# DRV8323RSRGZR.net
KiCad netlist of a schematic drawn in Altium Designer
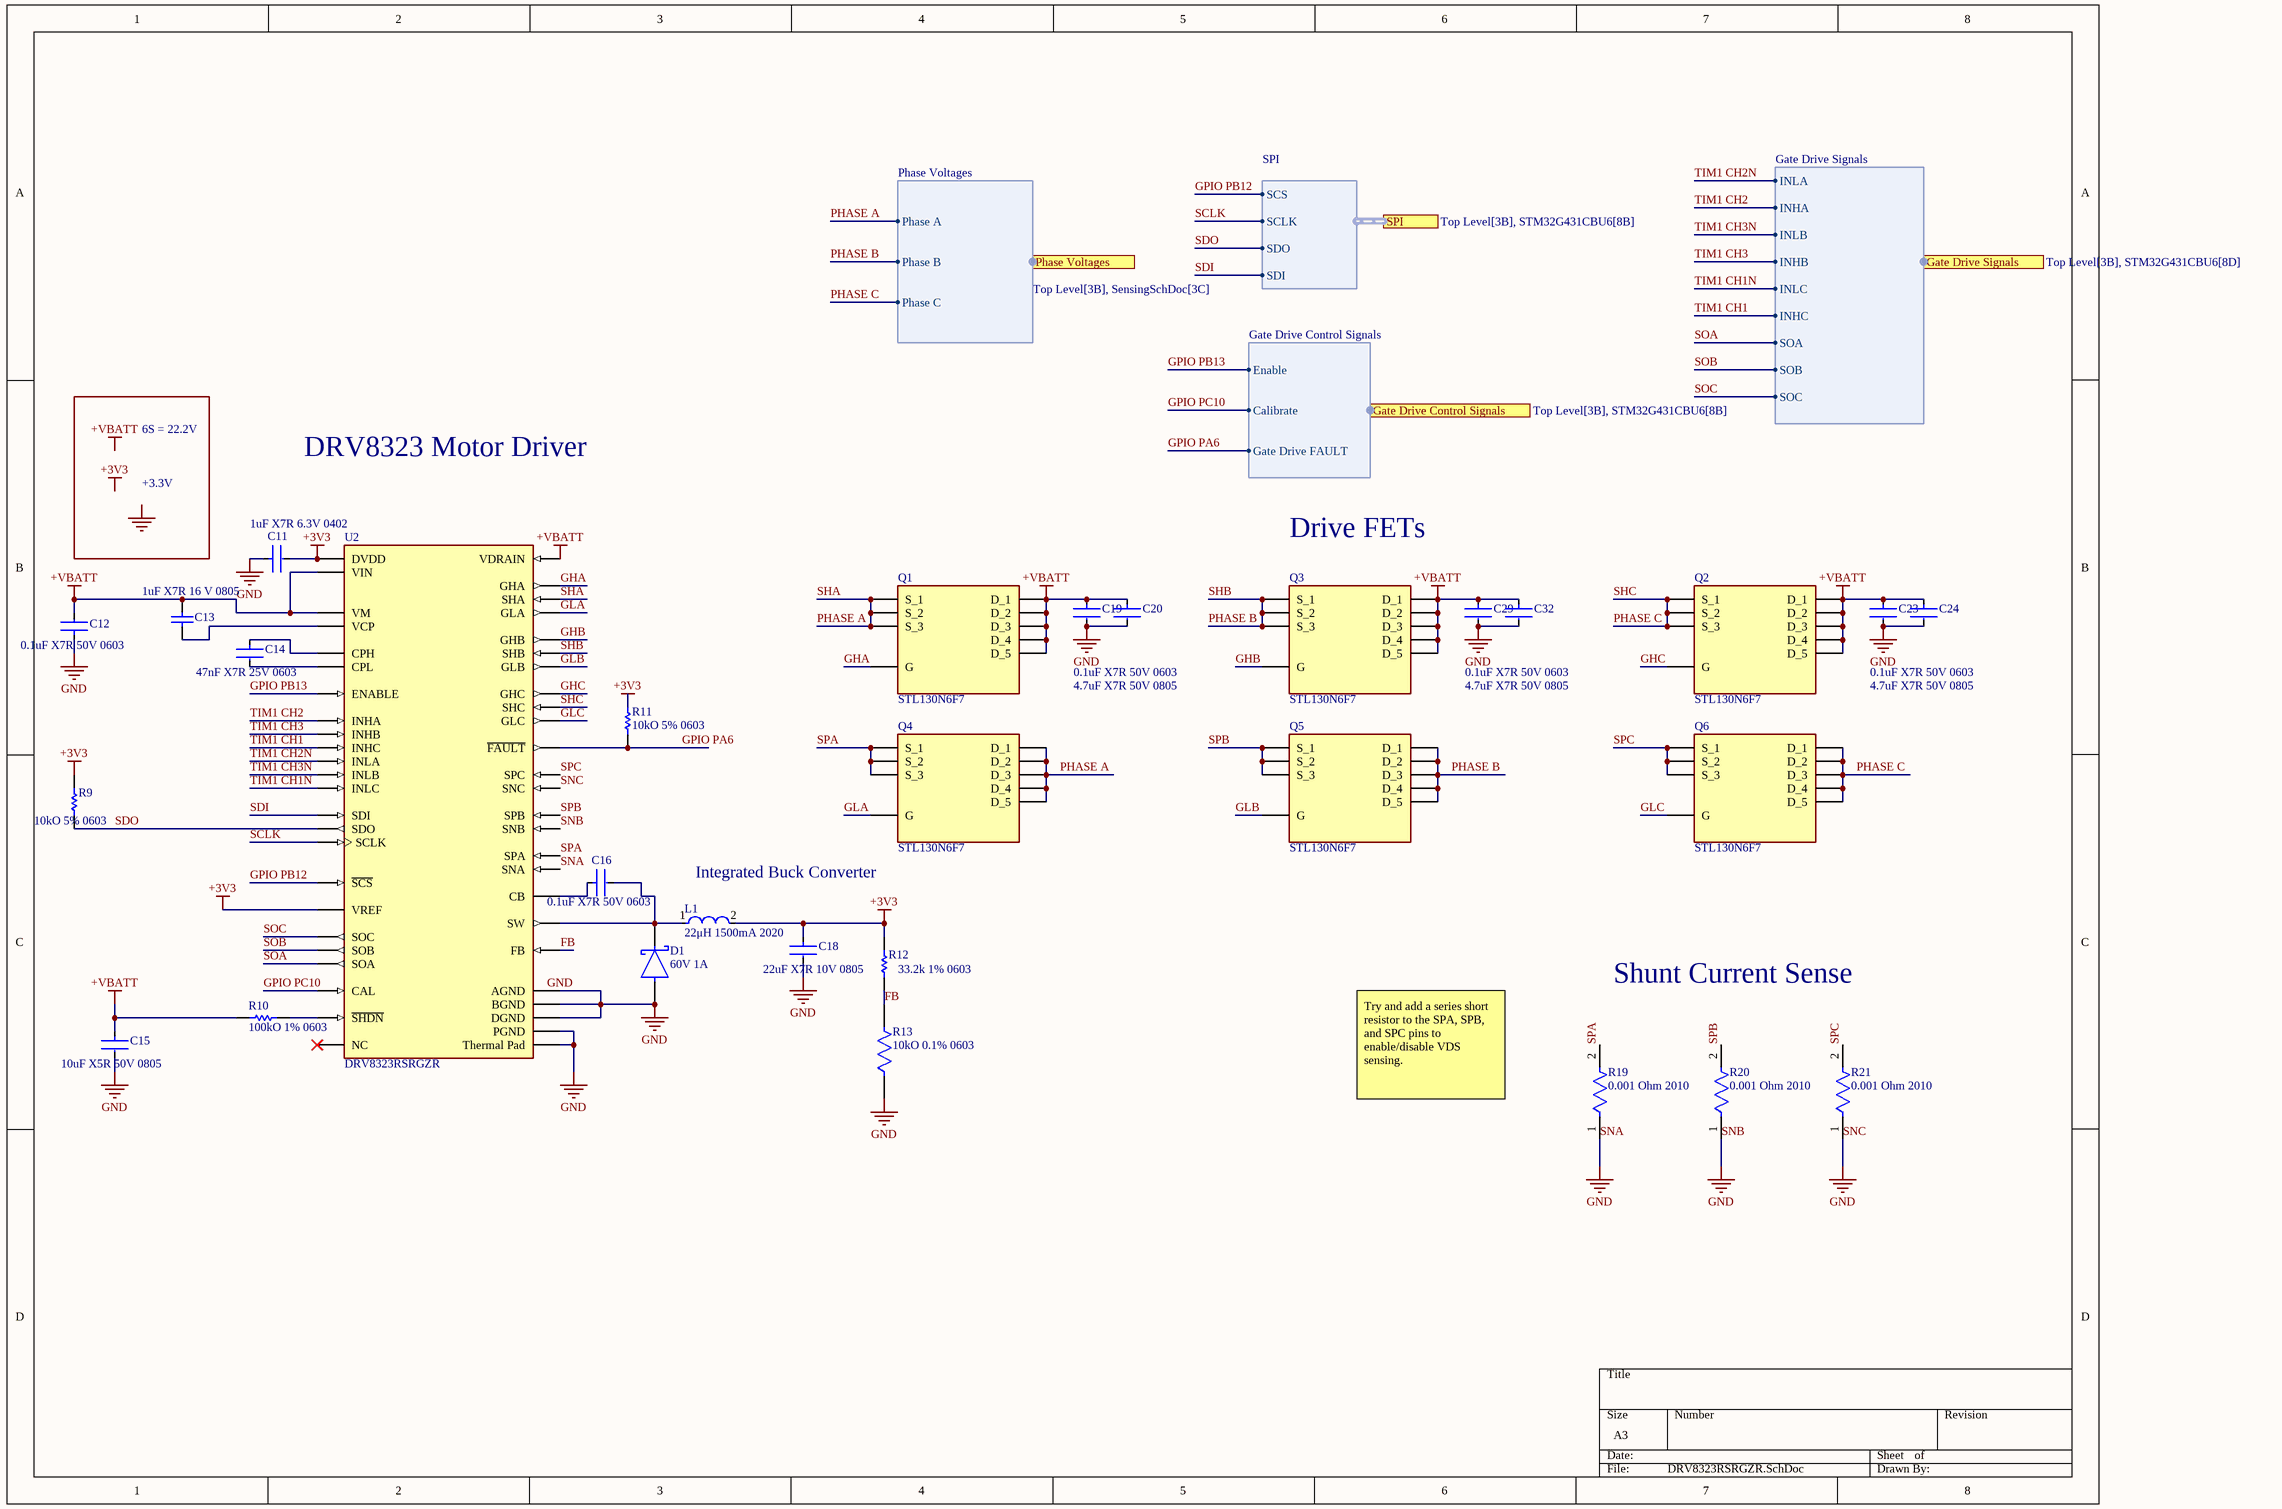
[diagram p0: DRV8323RSRGZR.SchDoc]

(export (version "E")
  (design (tool "Eeschema 10.0.6"))
  (components
    (comp (ref "C11")
      (value "1uF X7R 6.3V 0402")
      (footprint "FP-GRT155-0_05-IPC_C")
      (description "Multi-Layer Ceramic Capacitor 1uF 6.3V X7R ±10% 0402 Paper T/R")
      (libsource (lib "Altium Content Vault") (part "02cd4be3c70576c341d710602a673aa"))
    )
    (comp (ref "C12")
      (value "0.1uF X7R 50V 0603")
      (footprint "FP-0603B104K500CT-IPC_C")
      (description "CAP CER 0.1UF 50V X7R 0603")
      (fields (field (name "TOLERANCE") "10%"))
      (libsource (lib "Altium Content Vault") (part "02cd4be3c70576c341d710602a673aa"))
    )
    (comp (ref "C13")
      (value "1uF X7R 16 V 0805")
      (footprint "CAPC2013X140X50NL20T25")
      (fields (field (name "PART NUMBER") "C0805C105J4RACTU") (field (name "MANUFACTURER") "Kemet"))
      (libsource (lib "Altium Content Vault") (part "CAP"))
    )
    (comp (ref "C14")
      (value "47nF X7R 25V 0603")
      (footprint "FP-C0603C-CF-MFG")
      (description "CAP CER 0.047UF 25V 10% X7R 0603")
      (fields
        (field (name "MANUFACTURER") "KEMET")
        (field (name "OCTOPART") "https://octopart.com/c0603c473k3ractu-kemet-3834514")
      )
      (libsource (lib "Altium Content Vault") (part "b4654b650e69147ec39a6b967a45e02"))
    )
    (comp (ref "C15")
      (value "10uF X5R 50V 0805")
      (footprint "FP-GRM21B-0_2-e0_2_0_7-IPC_A")
      (description "Chip Multilayer Ceramic Capacitors for General Purpose, 0805, 10uF, X5R, 15%, 10%, 50V")
      (fields (field (name "TOLERANCE") "10%"))
      (libsource (lib "Altium Content Vault") (part "b4654b650e69147ec39a6b967a45e02"))
    )
    (comp (ref "C16")
      (value "0.1uF X7R 50V 0603")
      (footprint "FP-0603B104K500CT-IPC_C")
      (description "CAP CER 0.1UF 50V X7R 0603")
      (fields (field (name "TOLERANCE") "10%"))
      (libsource (lib "Altium Content Vault") (part "02cd4be3c70576c341d710602a673aa"))
    )
    (comp (ref "C18")
      (value "22uF X7R 10V 0805")
      (footprint "FP-GRM21B-0_2-e0_2_0_7-MFG")
      (description "Chip Multilayer Ceramic Capacitors for General Purpose, 0805, 22uF, X7R, 15%, 20%, 10V")
      (libsource (lib "Altium Content Vault") (part "b4654b650e69147ec39a6b967a45e02"))
    )
    (comp (ref "C19")
      (value "0.1uF X7R 50V 0603")
      (footprint "FP-0603B104K500CT-IPC_C")
      (description "CAP CER 0.1UF 50V X7R 0603")
      (fields (field (name "TOLERANCE") "10%"))
      (libsource (lib "Altium Content Vault") (part "02cd4be3c70576c341d710602a673aa"))
    )
    (comp (ref "C20")
      (value "4.7uF X7R 50V 0805")
      (footprint "FP-GRM21B-0_2-e0_2_0_7-MFG")
      (description "Chip Multilayer Ceramic Capacitors for General Purpose, 0805, 4.7uF, X7R, 15%, 20%, 50V")
      (libsource (lib "Altium Content Vault") (part "b4654b650e69147ec39a6b967a45e02"))
    )
    (comp (ref "C23")
      (value "0.1uF X7R 50V 0603")
      (footprint "FP-0603B104K500CT-IPC_C")
      (description "CAP CER 0.1UF 50V X7R 0603")
      (fields (field (name "TOLERANCE") "10%"))
      (libsource (lib "Altium Content Vault") (part "02cd4be3c70576c341d710602a673aa"))
    )
    (comp (ref "C24")
      (value "4.7uF X7R 50V 0805")
      (footprint "FP-GRM21B-0_2-e0_2_0_7-MFG")
      (description "Chip Multilayer Ceramic Capacitors for General Purpose, 0805, 4.7uF, X7R, 15%, 20%, 50V")
      (libsource (lib "Altium Content Vault") (part "b4654b650e69147ec39a6b967a45e02"))
    )
    (comp (ref "C29")
      (value "0.1uF X7R 50V 0603")
      (footprint "FP-0603B104K500CT-IPC_C")
      (description "CAP CER 0.1UF 50V X7R 0603")
      (fields (field (name "TOLERANCE") "10%"))
      (libsource (lib "Altium Content Vault") (part "02cd4be3c70576c341d710602a673aa"))
    )
    (comp (ref "C32")
      (value "4.7uF X7R 50V 0805")
      (footprint "FP-GRM21B-0_2-e0_2_0_7-MFG")
      (description "Chip Multilayer Ceramic Capacitors for General Purpose, 0805, 4.7uF, X7R, 15%, 20%, 50V")
      (libsource (lib "Altium Content Vault") (part "b4654b650e69147ec39a6b967a45e02"))
    )
    (comp (ref "D1")
      (value "60V 1A")
      (footprint "FP-SMA-MFG")
      (description "DIODE SCHOTTKY 60V 1A SMA")
      (libsource (lib "Altium Content Vault") (part "1d6ec82d83fb6aee721767c19dac4b9"))
    )
    (comp (ref "L1")
      (value "22μH 1500mA 2020")
      (footprint "FP-LQH5BPN_38-MFG")
      (description "Wire Wound Ferrite Inductor for Power Lines 22μH ±20% 0.132Ω 1500mA 2020\r\nLQH5BPN220M38L")
      (libsource (lib "Altium Content Vault") (part "725321dda6339637d4d059423bc1c3c"))
    )
    (comp (ref "Q1")
      (value "STL130N6F7")
      (footprint "FERD20U50DJFTR")
      (description "MOSFET (N-Channel)")
      (fields (field (name "MOUSER PART NUMBER") "511-STL130N6F7"))
      (libsource (lib "Schlib1") (part "STL130N6F7"))
    )
    (comp (ref "Q2")
      (value "STL130N6F7")
      (footprint "FERD20U50DJFTR")
      (description "MOSFET (N-Channel)")
      (fields (field (name "MOUSER PART NUMBER") "511-STL130N6F7"))
      (libsource (lib "Schlib1") (part "STL130N6F7"))
    )
    (comp (ref "Q3")
      (value "STL130N6F7")
      (footprint "FERD20U50DJFTR")
      (description "MOSFET (N-Channel)")
      (fields (field (name "MOUSER PART NUMBER") "511-STL130N6F7"))
      (libsource (lib "Schlib1") (part "STL130N6F7"))
    )
    (comp (ref "Q4")
      (value "STL130N6F7")
      (footprint "FERD20U50DJFTR")
      (description "MOSFET (N-Channel)")
      (fields (field (name "MOUSER PART NUMBER") "511-STL130N6F7"))
      (libsource (lib "Schlib1") (part "STL130N6F7"))
    )
    (comp (ref "Q5")
      (value "STL130N6F7")
      (footprint "FERD20U50DJFTR")
      (description "MOSFET (N-Channel)")
      (fields (field (name "MOUSER PART NUMBER") "511-STL130N6F7"))
      (libsource (lib "Schlib1") (part "STL130N6F7"))
    )
    (comp (ref "Q6")
      (value "STL130N6F7")
      (footprint "FERD20U50DJFTR")
      (description "MOSFET (N-Channel)")
      (fields (field (name "MOUSER PART NUMBER") "511-STL130N6F7"))
      (libsource (lib "Schlib1") (part "STL130N6F7"))
    )
    (comp (ref "R9")
      (value "10kO 5% 0603")
      (footprint "RESC1608X55X25LL10T15")
      (fields (field (name "MANUFACTURER") "Yageo") (field (name "PART NUMBER") "RC0603JR-1010KL"))
      (libsource (lib "Altium Content Vault") (part "RES"))
    )
    (comp (ref "R10")
      (value "100kO 1% 0603")
      (footprint "RESC1608X55X25ML10T15")
      (fields (field (name "MANUFACTURER") "Yageo") (field (name "PART NUMBER") "RC0603FR-13100KL"))
      (libsource (lib "Altium Content Vault") (part "RES"))
    )
    (comp (ref "R11")
      (value "10kO 5% 0603")
      (footprint "RESC1608X55X25LL10T15")
      (fields (field (name "MANUFACTURER") "Yageo") (field (name "PART NUMBER") "RC0603JR-1010KL"))
      (libsource (lib "Altium Content Vault") (part "RES"))
    )
    (comp (ref "R12")
      (value "33.2k 1% 0603")
      (footprint "RESC1608X55X25NL10T15")
      (description "Chip Resistor, 33.2 KOhm, +/- 1%, 100 mW, -55 to 155 degC, 0603 (1608 Metric), RoHS, Tape and Reel")
      (fields (field (name "TOLERANCE") "20ppm"))
      (libsource (lib "Altium Content Vault") (part "RES-2"))
    )
    (comp (ref "R13")
      (value "10kO 0.1% 0603")
      (footprint "FP-RT0603-MFG")
      (description "RES SMD 10K OHM 0.1% 1/10W 0603")
      (fields (field (name "MANUFACTURER") "Yageo") (field (name "TOLERANCE") "0.001"))
      (libsource (lib "") (part "1029c3af85768c4190bb7ad29bc67b5_1"))
    )
    (comp (ref "R19")
      (value "0.001 Ohm 2010")
      (footprint "FP-WSL2010-1_47-MFG")
      (fields (field (name "TOLERANCE") "1%"))
      (libsource (lib "Altium Content Vault") (part "1029c3af85768c4190bb7ad29bc67b5"))
    )
    (comp (ref "R20")
      (value "0.001 Ohm 2010")
      (footprint "FP-WSL2010-1_47-MFG")
      (fields (field (name "TOLERANCE") "1%"))
      (libsource (lib "Altium Content Vault") (part "1029c3af85768c4190bb7ad29bc67b5"))
    )
    (comp (ref "R21")
      (value "0.001 Ohm 2010")
      (footprint "FP-WSL2010-1_47-MFG")
      (fields (field (name "TOLERANCE") "1%"))
      (libsource (lib "Altium Content Vault") (part "1029c3af85768c4190bb7ad29bc67b5"))
    )
    (comp (ref "U2")
      (value "DRV8323RSRGZR")
      (footprint "FP-RGZ0048A-MFG")
      (description "IC MTR DRV MULTIPHAS 6-60V 48QFN")
      (fields
        (field (name "MANUFACTURER") "Texas Instruments")
        (field (name "OCTOPART") "https://octopart.com/drv8323rsrgzr-texas+instruments-80665177")
      )
      (libsource (lib "Altium Content Vault") (part "9f6f2f4cce60835f155f5fba280b04a"))
    )
  )
  (nets
    (net (code "8") (name "+3V3") (class "Default")
      (node (ref "C11") (pin "2") (pinfunction "2_2") (pintype "passive"))
      (node (ref "C18") (pin "1") (pinfunction "1_1") (pintype "passive"))
      (node (ref "L1") (pin "2") (pinfunction "2_2") (pintype "passive"))
      (node (ref "R11") (pin "2") (pinfunction "2_2") (pintype "passive"))
      (node (ref "R12") (pin "2") (pinfunction "2_2") (pintype "passive"))
      (node (ref "R9") (pin "2") (pinfunction "2_2") (pintype "passive"))
      (node (ref "U2") (pin "26") (pinfunction "VREF_26") (pintype "power_in"))
      (node (ref "U2") (pin "36") (pinfunction "DVDD_36") (pintype "power_in"))
    )
    (net (code "9") (name "+VBATT") (class "Default")
      (node (ref "C12") (pin "2") (pinfunction "2_2") (pintype "passive"))
      (node (ref "C13") (pin "1") (pinfunction "1_1") (pintype "passive"))
      (node (ref "C15") (pin "1") (pinfunction "1_1") (pintype "passive"))
      (node (ref "C19") (pin "1") (pinfunction "1_1") (pintype "passive"))
      (node (ref "C20") (pin "1") (pinfunction "1_1") (pintype "passive"))
      (node (ref "C23") (pin "1") (pinfunction "1_1") (pintype "passive"))
      (node (ref "C24") (pin "1") (pinfunction "1_1") (pintype "passive"))
      (node (ref "C29") (pin "1") (pinfunction "1_1") (pintype "passive"))
      (node (ref "C32") (pin "1") (pinfunction "1_1") (pintype "passive"))
      (node (ref "Q1") (pin "5") (pinfunction "D_1_5") (pintype "passive"))
      (node (ref "Q1") (pin "6") (pinfunction "D_2_6") (pintype "passive"))
      (node (ref "Q1") (pin "7") (pinfunction "D_3_7") (pintype "passive"))
      (node (ref "Q1") (pin "8") (pinfunction "D_4_8") (pintype "passive"))
      (node (ref "Q1") (pin "9") (pinfunction "D_5_9") (pintype "passive"))
      (node (ref "Q2") (pin "5") (pinfunction "D_1_5") (pintype "passive"))
      (node (ref "Q2") (pin "6") (pinfunction "D_2_6") (pintype "passive"))
      (node (ref "Q2") (pin "7") (pinfunction "D_3_7") (pintype "passive"))
      (node (ref "Q2") (pin "8") (pinfunction "D_4_8") (pintype "passive"))
      (node (ref "Q2") (pin "9") (pinfunction "D_5_9") (pintype "passive"))
      (node (ref "Q3") (pin "5") (pinfunction "D_1_5") (pintype "passive"))
      (node (ref "Q3") (pin "6") (pinfunction "D_2_6") (pintype "passive"))
      (node (ref "Q3") (pin "7") (pinfunction "D_3_7") (pintype "passive"))
      (node (ref "Q3") (pin "8") (pinfunction "D_4_8") (pintype "passive"))
      (node (ref "Q3") (pin "9") (pinfunction "D_5_9") (pintype "passive"))
      (node (ref "R10") (pin "2") (pinfunction "2_2") (pintype "passive"))
      (node (ref "U2") (pin "47") (pinfunction "VIN_47") (pintype "power_in"))
      (node (ref "U2") (pin "6") (pinfunction "VM_6") (pintype "power_in"))
      (node (ref "U2") (pin "7") (pinfunction "VDRAIN_7") (pintype "input"))
    )
    (net (code "10") (name "/FB") (class "Default")
      (node (ref "R12") (pin "1") (pinfunction "1_1") (pintype "passive"))
      (node (ref "R13") (pin "2") (pinfunction "2_2") (pintype "passive"))
      (node (ref "U2") (pin "1") (pinfunction "FB_1") (pintype "input"))
    )
    (net (code "11") (name "/GHA") (class "Default")
      (node (ref "Q1") (pin "4") (pinfunction "G_4") (pintype "passive"))
      (node (ref "U2") (pin "8") (pinfunction "GHA_8") (pintype "output"))
    )
    (net (code "12") (name "/GHB") (class "Default")
      (node (ref "Q3") (pin "4") (pinfunction "G_4") (pintype "passive"))
      (node (ref "U2") (pin "17") (pinfunction "GHB_17") (pintype "output"))
    )
    (net (code "13") (name "/GHC") (class "Default")
      (node (ref "Q2") (pin "4") (pinfunction "G_4") (pintype "passive"))
      (node (ref "U2") (pin "18") (pinfunction "GHC_18") (pintype "output"))
    )
    (net (code "14") (name "/GLA") (class "Default")
      (node (ref "Q4") (pin "4") (pinfunction "G_4") (pintype "passive"))
      (node (ref "U2") (pin "10") (pinfunction "GLA_10") (pintype "output"))
    )
    (net (code "15") (name "/GLB") (class "Default")
      (node (ref "Q5") (pin "4") (pinfunction "G_4") (pintype "passive"))
      (node (ref "U2") (pin "15") (pinfunction "GLB_15") (pintype "output"))
    )
    (net (code "16") (name "/GLC") (class "Default")
      (node (ref "Q6") (pin "4") (pinfunction "G_4") (pintype "passive"))
      (node (ref "U2") (pin "20") (pinfunction "GLC_20") (pintype "output"))
    )
    (net (code "17") (name "/GPIO PA6") (class "Default")
      (node (ref "R11") (pin "1") (pinfunction "1_1") (pintype "passive"))
      (node (ref "U2") (pin "28") (pinfunction "~{FAULT}_28") (pintype "output"))
    )
    (net (code "18") (name "/GPIO PB12") (class "Default")
      (node (ref "U2") (pin "32") (pinfunction "~{SCS}_32") (pintype "input"))
    )
    (net (code "19") (name "/GPIO PB13") (class "Default")
      (node (ref "U2") (pin "33") (pinfunction "ENABLE_33") (pintype "input"))
    )
    (net (code "20") (name "/GPIO PC10") (class "Default")
      (node (ref "U2") (pin "34") (pinfunction "CAL_34") (pintype "input"))
    )
    (net (code "21") (name "/PHASE A") (class "Default")
      (node (ref "Q1") (pin "1") (pinfunction "S_1_1") (pintype "passive"))
      (node (ref "Q1") (pin "2") (pinfunction "S_2_2") (pintype "passive"))
      (node (ref "Q1") (pin "3") (pinfunction "S_3_3") (pintype "passive"))
      (node (ref "Q4") (pin "5") (pinfunction "D_1_5") (pintype "passive"))
      (node (ref "Q4") (pin "6") (pinfunction "D_2_6") (pintype "passive"))
      (node (ref "Q4") (pin "7") (pinfunction "D_3_7") (pintype "passive"))
      (node (ref "Q4") (pin "8") (pinfunction "D_4_8") (pintype "passive"))
      (node (ref "Q4") (pin "9") (pinfunction "D_5_9") (pintype "passive"))
      (node (ref "U2") (pin "9") (pinfunction "SHA_9") (pintype "input"))
    )
    (net (code "22") (name "/PHASE B") (class "Default")
      (node (ref "Q3") (pin "1") (pinfunction "S_1_1") (pintype "passive"))
      (node (ref "Q3") (pin "2") (pinfunction "S_2_2") (pintype "passive"))
      (node (ref "Q3") (pin "3") (pinfunction "S_3_3") (pintype "passive"))
      (node (ref "Q5") (pin "5") (pinfunction "D_1_5") (pintype "passive"))
      (node (ref "Q5") (pin "6") (pinfunction "D_2_6") (pintype "passive"))
      (node (ref "Q5") (pin "7") (pinfunction "D_3_7") (pintype "passive"))
      (node (ref "Q5") (pin "8") (pinfunction "D_4_8") (pintype "passive"))
      (node (ref "Q5") (pin "9") (pinfunction "D_5_9") (pintype "passive"))
      (node (ref "U2") (pin "16") (pinfunction "SHB_16") (pintype "input"))
    )
    (net (code "23") (name "/PHASE C") (class "Default")
      (node (ref "Q2") (pin "1") (pinfunction "S_1_1") (pintype "passive"))
      (node (ref "Q2") (pin "2") (pinfunction "S_2_2") (pintype "passive"))
      (node (ref "Q2") (pin "3") (pinfunction "S_3_3") (pintype "passive"))
      (node (ref "Q6") (pin "5") (pinfunction "D_1_5") (pintype "passive"))
      (node (ref "Q6") (pin "6") (pinfunction "D_2_6") (pintype "passive"))
      (node (ref "Q6") (pin "7") (pinfunction "D_3_7") (pintype "passive"))
      (node (ref "Q6") (pin "8") (pinfunction "D_4_8") (pintype "passive"))
      (node (ref "Q6") (pin "9") (pinfunction "D_5_9") (pintype "passive"))
      (node (ref "U2") (pin "19") (pinfunction "SHC_19") (pintype "input"))
    )
    (net (code "24") (name "/SCLK") (class "Default")
      (node (ref "U2") (pin "31") (pinfunction "SCLK_31") (pintype "input"))
    )
    (net (code "25") (name "/SDI") (class "Default")
      (node (ref "U2") (pin "30") (pinfunction "SDI_30") (pintype "input"))
    )
    (net (code "26") (name "/SDO") (class "Default")
      (node (ref "R9") (pin "1") (pinfunction "1_1") (pintype "passive"))
      (node (ref "U2") (pin "29") (pinfunction "SDO_29") (pintype "output"))
    )
    (net (code "27") (name "/SOA") (class "Default")
      (node (ref "U2") (pin "25") (pinfunction "SOA_25") (pintype "output"))
    )
    (net (code "28") (name "/SOB") (class "Default")
      (node (ref "U2") (pin "24") (pinfunction "SOB_24") (pintype "output"))
    )
    (net (code "29") (name "/SOC") (class "Default")
      (node (ref "U2") (pin "23") (pinfunction "SOC_23") (pintype "output"))
    )
    (net (code "30") (name "/SPA") (class "Default")
      (node (ref "Q4") (pin "1") (pinfunction "S_1_1") (pintype "passive"))
      (node (ref "Q4") (pin "2") (pinfunction "S_2_2") (pintype "passive"))
      (node (ref "Q4") (pin "3") (pinfunction "S_3_3") (pintype "passive"))
      (node (ref "R19") (pin "2") (pinfunction "2_2") (pintype "passive"))
      (node (ref "U2") (pin "11") (pinfunction "SPA_11") (pintype "input"))
    )
    (net (code "31") (name "/SPB") (class "Default")
      (node (ref "Q5") (pin "1") (pinfunction "S_1_1") (pintype "passive"))
      (node (ref "Q5") (pin "2") (pinfunction "S_2_2") (pintype "passive"))
      (node (ref "Q5") (pin "3") (pinfunction "S_3_3") (pintype "passive"))
      (node (ref "R20") (pin "2") (pinfunction "2_2") (pintype "passive"))
      (node (ref "U2") (pin "14") (pinfunction "SPB_14") (pintype "input"))
    )
    (net (code "32") (name "/SPC") (class "Default")
      (node (ref "Q6") (pin "1") (pinfunction "S_1_1") (pintype "passive"))
      (node (ref "Q6") (pin "2") (pinfunction "S_2_2") (pintype "passive"))
      (node (ref "Q6") (pin "3") (pinfunction "S_3_3") (pintype "passive"))
      (node (ref "R21") (pin "2") (pinfunction "2_2") (pintype "passive"))
      (node (ref "U2") (pin "21") (pinfunction "SPC_21") (pintype "input"))
    )
    (net (code "33") (name "/TIM1 CH1") (class "Default")
      (node (ref "U2") (pin "41") (pinfunction "INHC_41") (pintype "input"))
    )
    (net (code "34") (name "/TIM1 CH1N") (class "Default")
      (node (ref "U2") (pin "42") (pinfunction "INLC_42") (pintype "input"))
    )
    (net (code "35") (name "/TIM1 CH2") (class "Default")
      (node (ref "U2") (pin "37") (pinfunction "INHA_37") (pintype "input"))
    )
    (net (code "36") (name "/TIM1 CH2N") (class "Default")
      (node (ref "U2") (pin "38") (pinfunction "INLA_38") (pintype "input"))
    )
    (net (code "37") (name "/TIM1 CH3") (class "Default")
      (node (ref "U2") (pin "39") (pinfunction "INHB_39") (pintype "input"))
    )
    (net (code "38") (name "/TIM1 CH3N") (class "Default")
      (node (ref "U2") (pin "40") (pinfunction "INLB_40") (pintype "input"))
    )
    (net (code "43") (name "GND") (class "Default")
      (node (ref "C11") (pin "1") (pinfunction "1_1") (pintype "passive"))
      (node (ref "C12") (pin "1") (pinfunction "1_1") (pintype "passive"))
      (node (ref "C15") (pin "2") (pinfunction "2_2") (pintype "passive"))
      (node (ref "C18") (pin "2") (pinfunction "2_2") (pintype "passive"))
      (node (ref "C19") (pin "2") (pinfunction "2_2") (pintype "passive"))
      (node (ref "C20") (pin "2") (pinfunction "2_2") (pintype "passive"))
      (node (ref "C23") (pin "2") (pinfunction "2_2") (pintype "passive"))
      (node (ref "C24") (pin "2") (pinfunction "2_2") (pintype "passive"))
      (node (ref "C29") (pin "2") (pinfunction "2_2") (pintype "passive"))
      (node (ref "C32") (pin "2") (pinfunction "2_2") (pintype "passive"))
      (node (ref "D1") (pin "2") (pinfunction "A_2") (pintype "passive"))
      (node (ref "R13") (pin "1") (pinfunction "1_1") (pintype "passive"))
      (node (ref "R19") (pin "1") (pinfunction "1_1") (pintype "passive"))
      (node (ref "R20") (pin "1") (pinfunction "1_1") (pintype "passive"))
      (node (ref "R21") (pin "1") (pinfunction "1_1") (pintype "passive"))
      (node (ref "U2") (pin "12") (pinfunction "SNA_12") (pintype "input"))
      (node (ref "U2") (pin "13") (pinfunction "SNB_13") (pintype "input"))
      (node (ref "U2") (pin "2") (pinfunction "PGND_2") (pintype "power_in"))
      (node (ref "U2") (pin "22") (pinfunction "SNC_22") (pintype "input"))
      (node (ref "U2") (pin "27") (pinfunction "DGND_27") (pintype "power_in"))
      (node (ref "U2") (pin "35") (pinfunction "AGND_35") (pintype "power_in"))
      (node (ref "U2") (pin "43") (pinfunction "BGND_43") (pintype "power_in"))
      (node (ref "U2") (pin "49") (pinfunction "Thermal_Pad_49") (pintype "power_in"))
    )
    (net (code "44") (name "Net-(D1-C)") (class "Default")
      (node (ref "C16") (pin "2") (pinfunction "2_2") (pintype "passive"))
      (node (ref "D1") (pin "1") (pinfunction "C_1") (pintype "passive"))
      (node (ref "L1") (pin "1") (pinfunction "1_1") (pintype "passive"))
      (node (ref "U2") (pin "45") (pinfunction "SW_45") (pintype "output"))
    )
    (net (code "45") (name "Net-(U2-CB)") (class "Default")
      (node (ref "C16") (pin "1") (pinfunction "1_1") (pintype "passive"))
      (node (ref "U2") (pin "44") (pinfunction "CB_44") (pintype "power_in"))
    )
    (net (code "46") (name "Net-(U2-CPH)") (class "Default")
      (node (ref "C14") (pin "1") (pinfunction "1_1") (pintype "passive"))
      (node (ref "U2") (pin "4") (pinfunction "CPH_4") (pintype "power_in"))
    )
    (net (code "47") (name "Net-(U2-CPL)") (class "Default")
      (node (ref "C14") (pin "2") (pinfunction "2_2") (pintype "passive"))
      (node (ref "U2") (pin "3") (pinfunction "CPL_3") (pintype "power_in"))
    )
    (net (code "48") (name "Net-(U2-VCP)") (class "Default")
      (node (ref "C13") (pin "2") (pinfunction "2_2") (pintype "passive"))
      (node (ref "U2") (pin "5") (pinfunction "VCP_5") (pintype "power_in"))
    )
    (net (code "49") (name "Net-(U2-~{SHDN})") (class "Default")
      (node (ref "R10") (pin "1") (pinfunction "1_1") (pintype "passive"))
      (node (ref "U2") (pin "48") (pinfunction "~{SHDN}_48") (pintype "input"))
    )
    (net (code "50") (name "unconnected-(U2-NC-Pad46)") (class "Default")
      (node (ref "U2") (pin "46") (pinfunction "NC_46") (pintype "passive+no_connect"))
    )
  )
)
